# Sheet1.net
KiCad netlist of a schematic drawn in Altium Designer
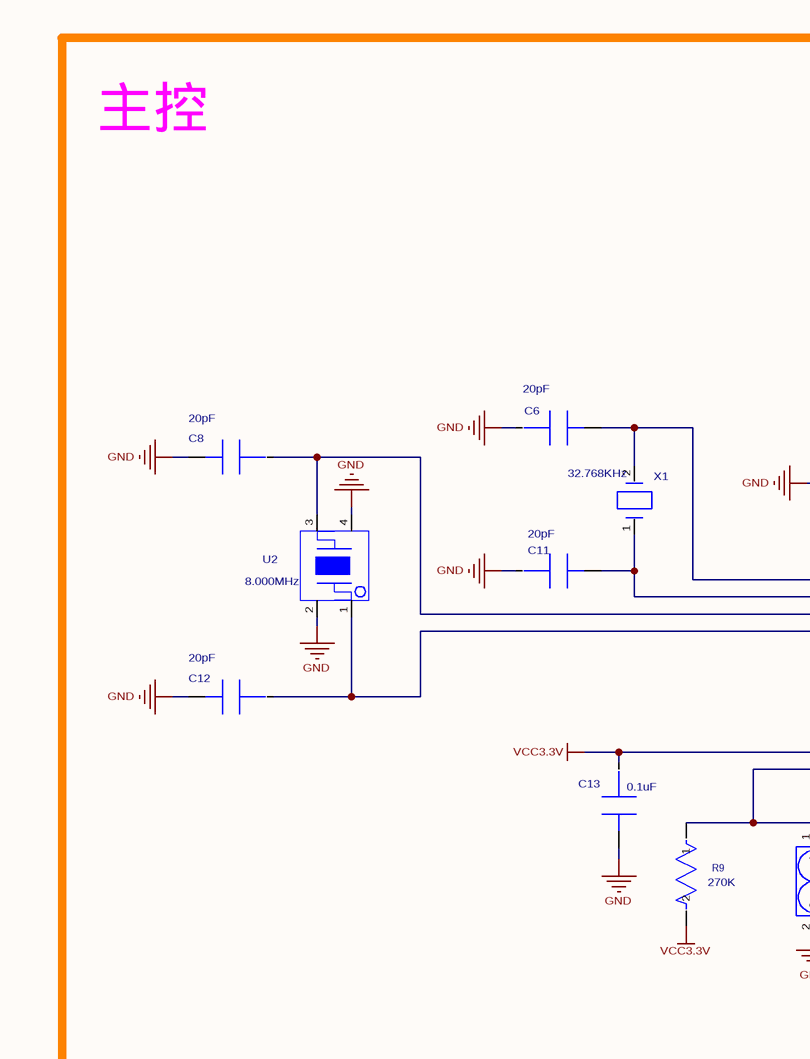
[diagram p0: Sheet1.SchDoc, top column 1 of 4]
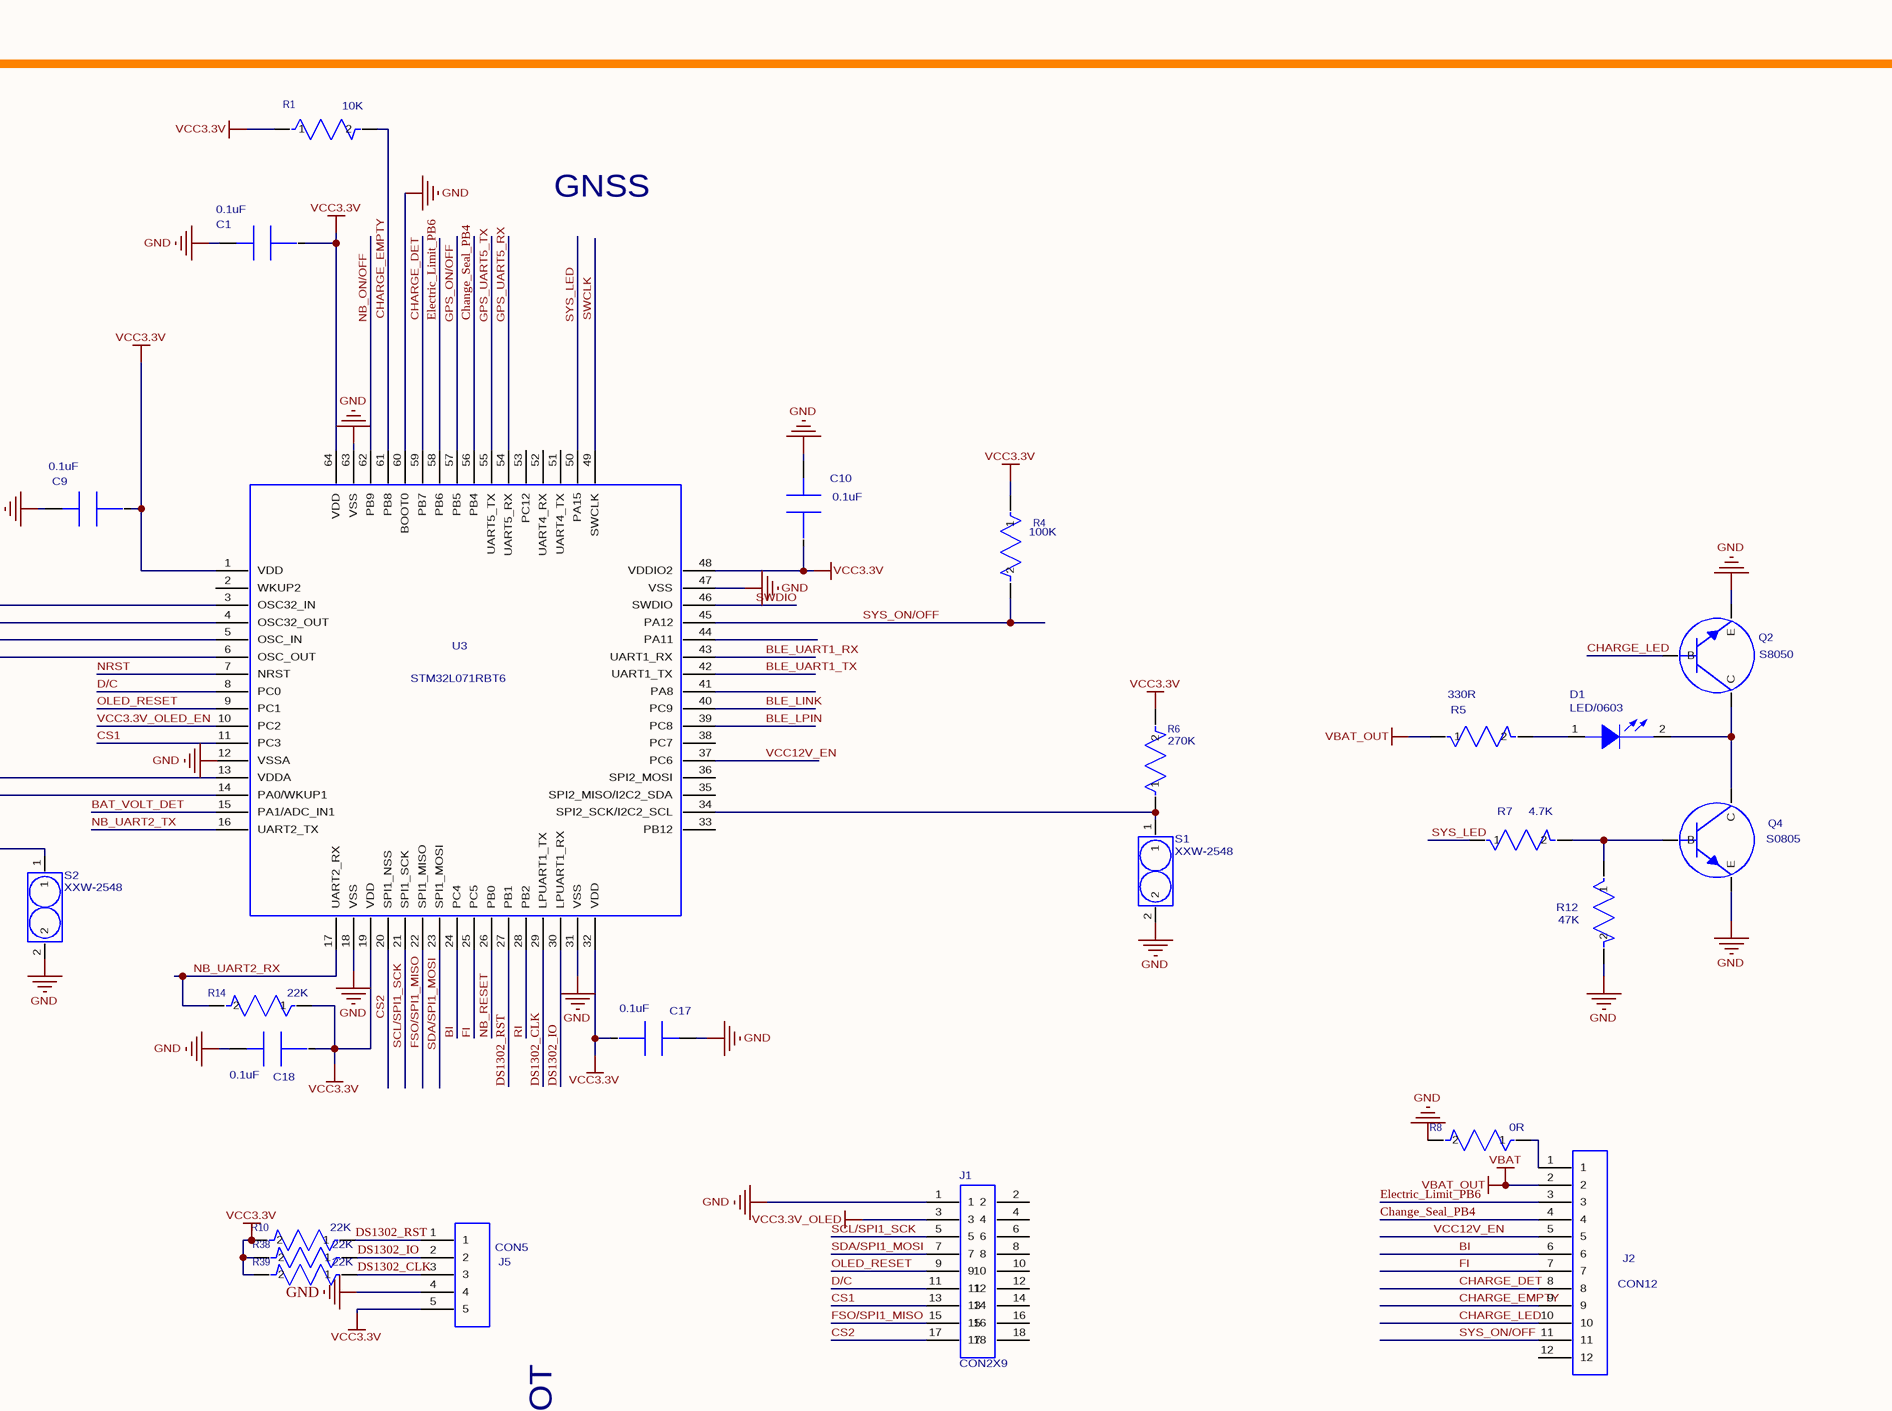
[diagram p1: Sheet1.SchDoc, top column 2 of 4]
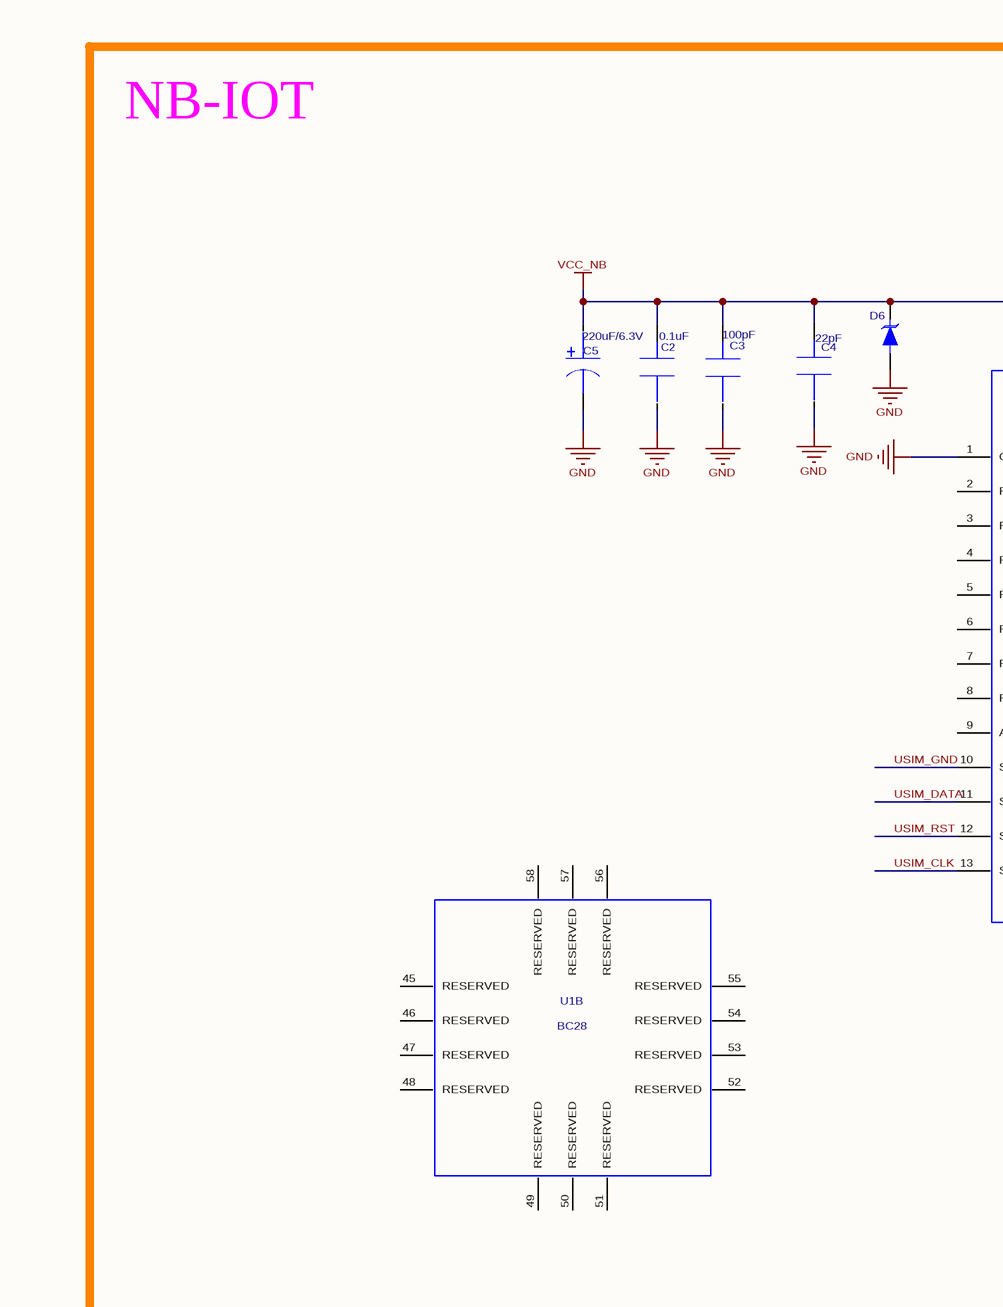
[diagram p2: Sheet1.SchDoc, top column 3 of 4]
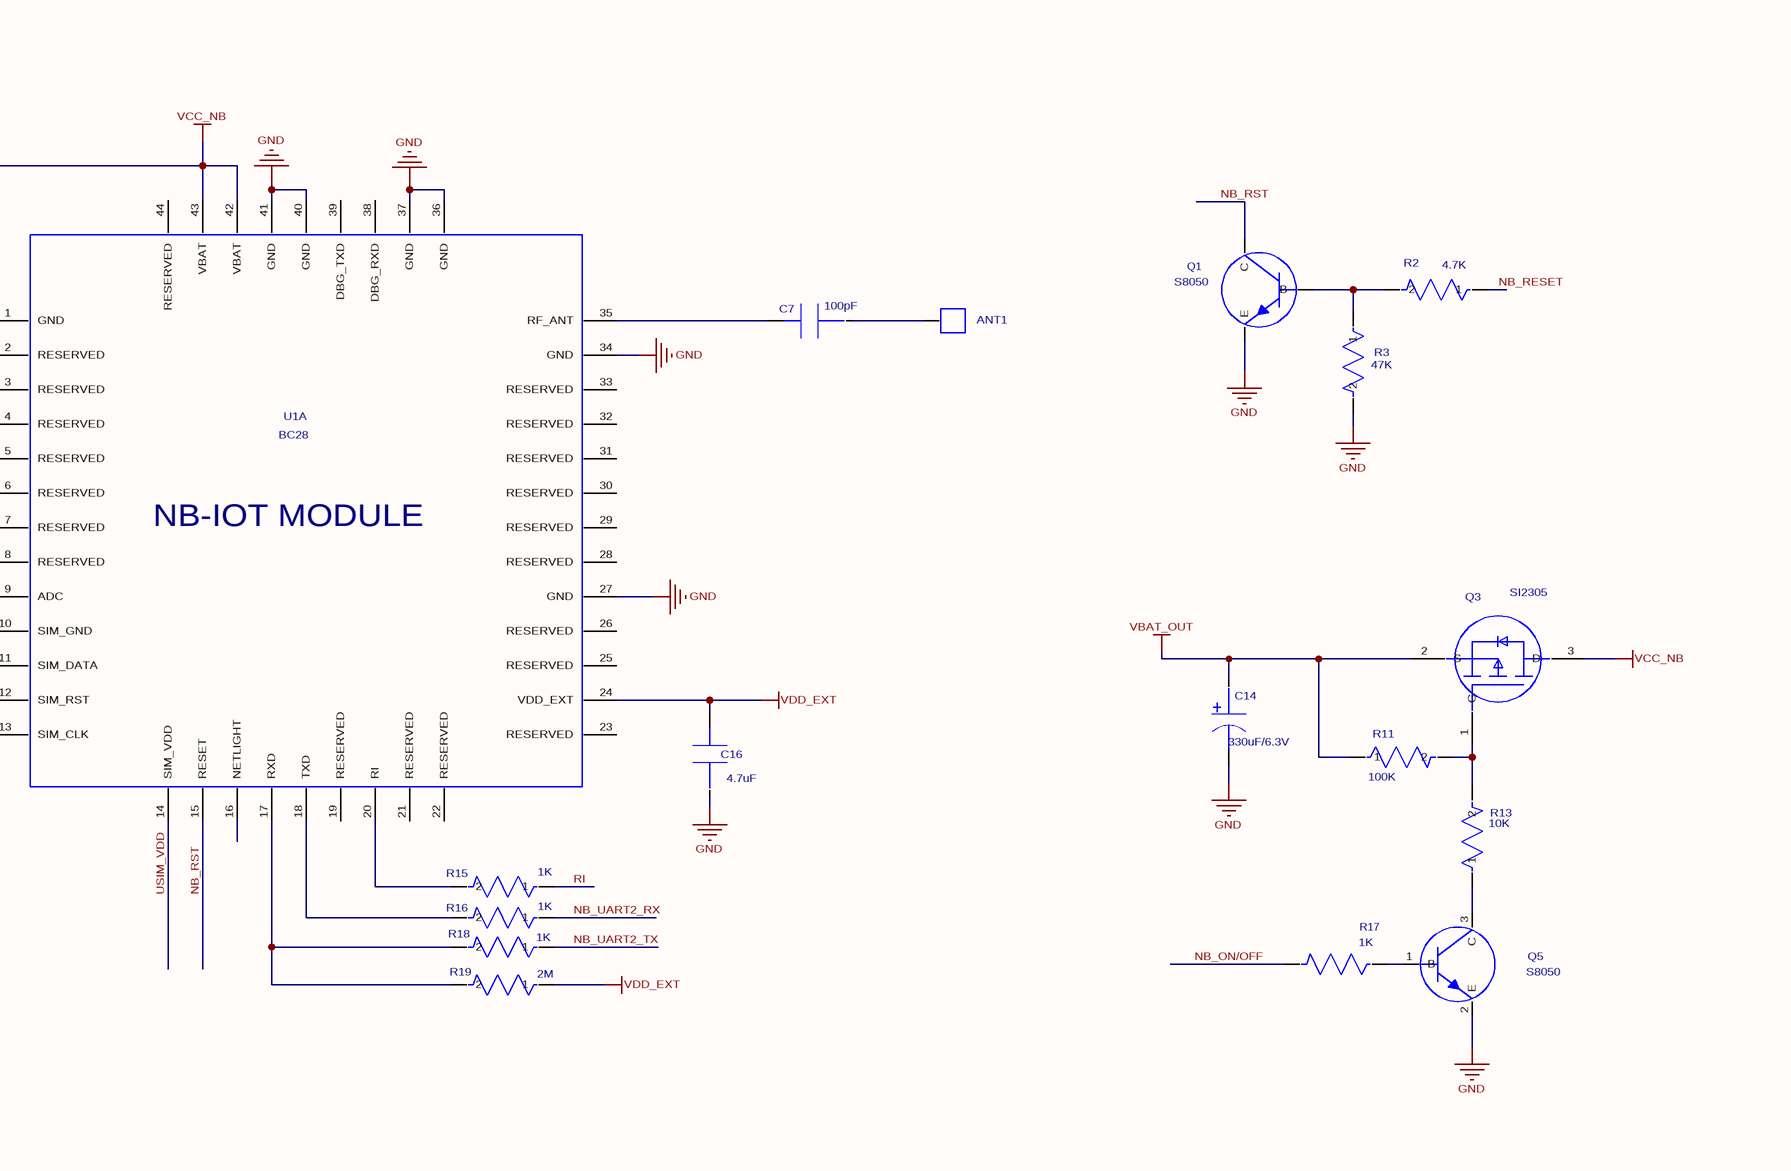
[diagram p3: Sheet1.SchDoc, top column 4 of 4]
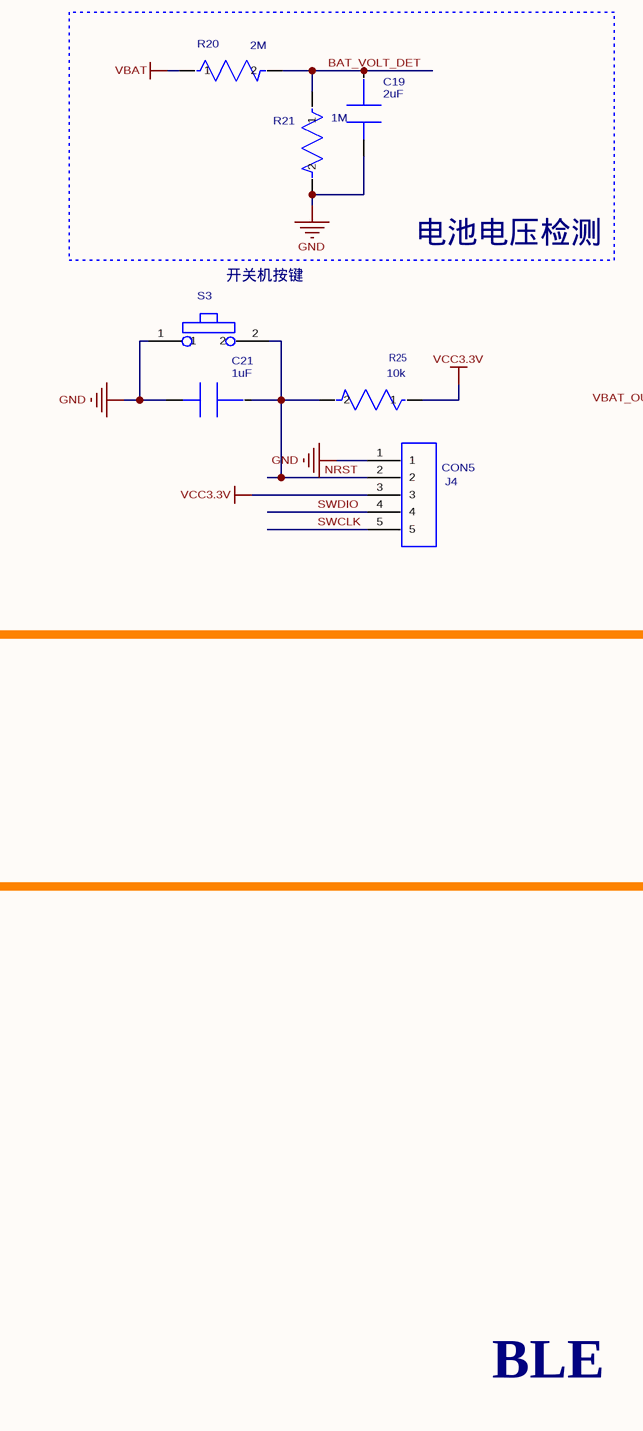
[diagram p4: Sheet1.SchDoc, centre column 1 of 4]
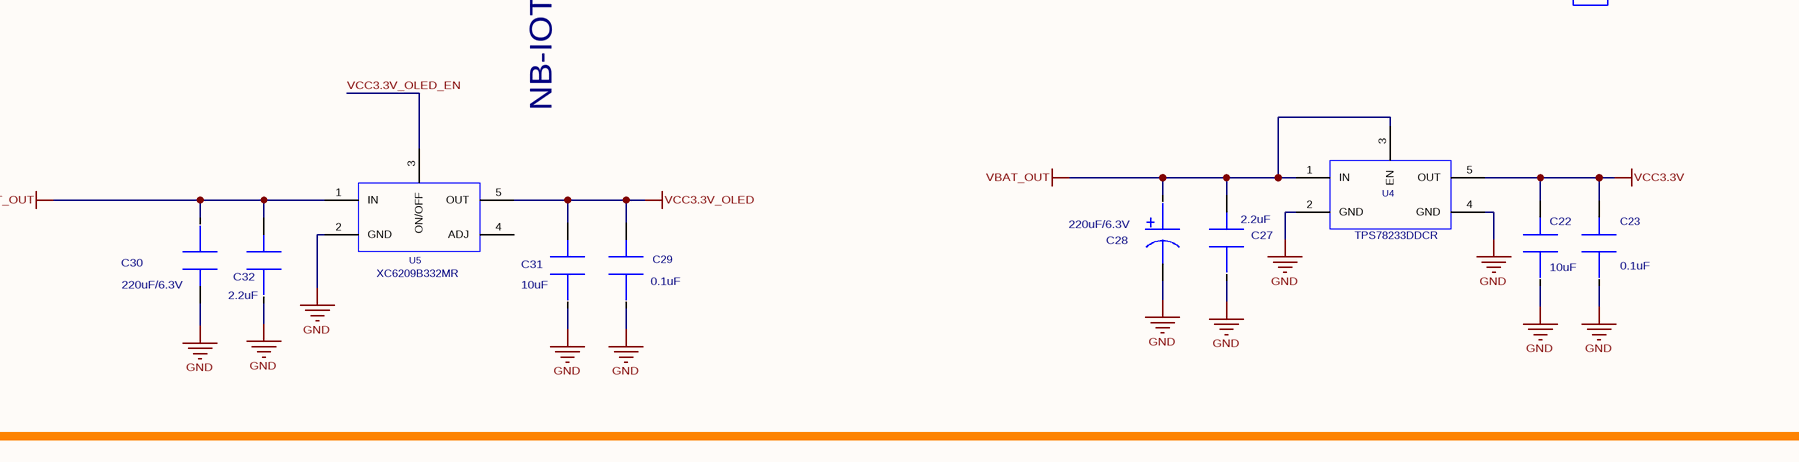
[diagram p5: Sheet1.SchDoc, centre column 2 of 4]
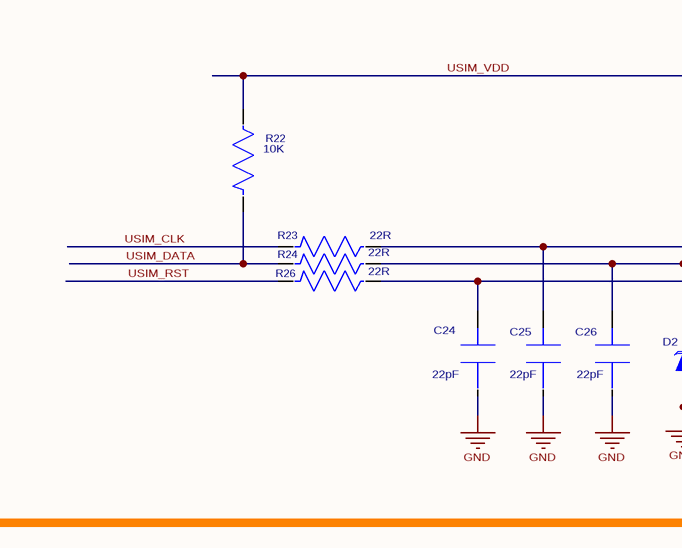
[diagram p6: Sheet1.SchDoc, centre column 3 of 4]
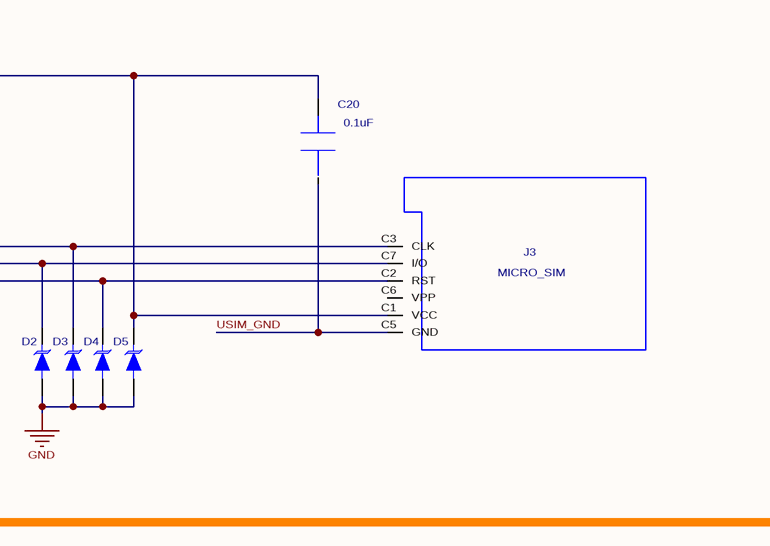
[diagram p7: Sheet1.SchDoc, centre column 4 of 4]
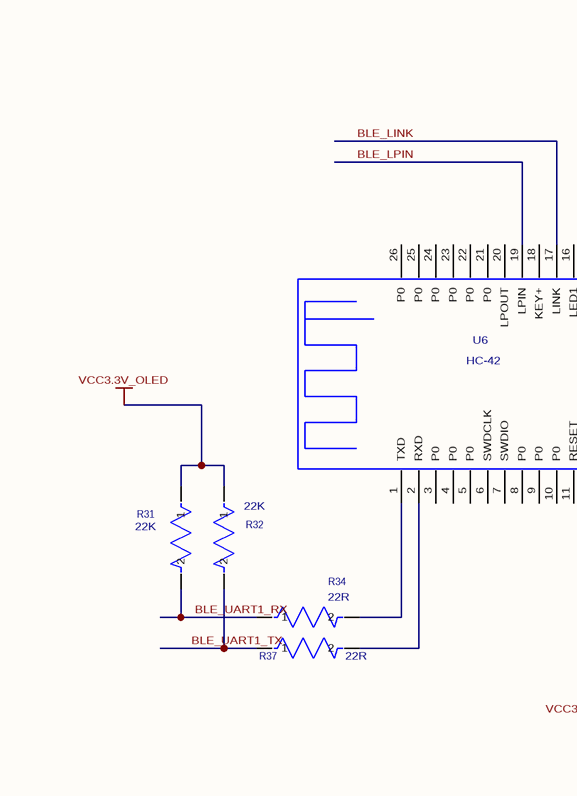
[diagram p8: Sheet1.SchDoc, bottom column 1 of 4]
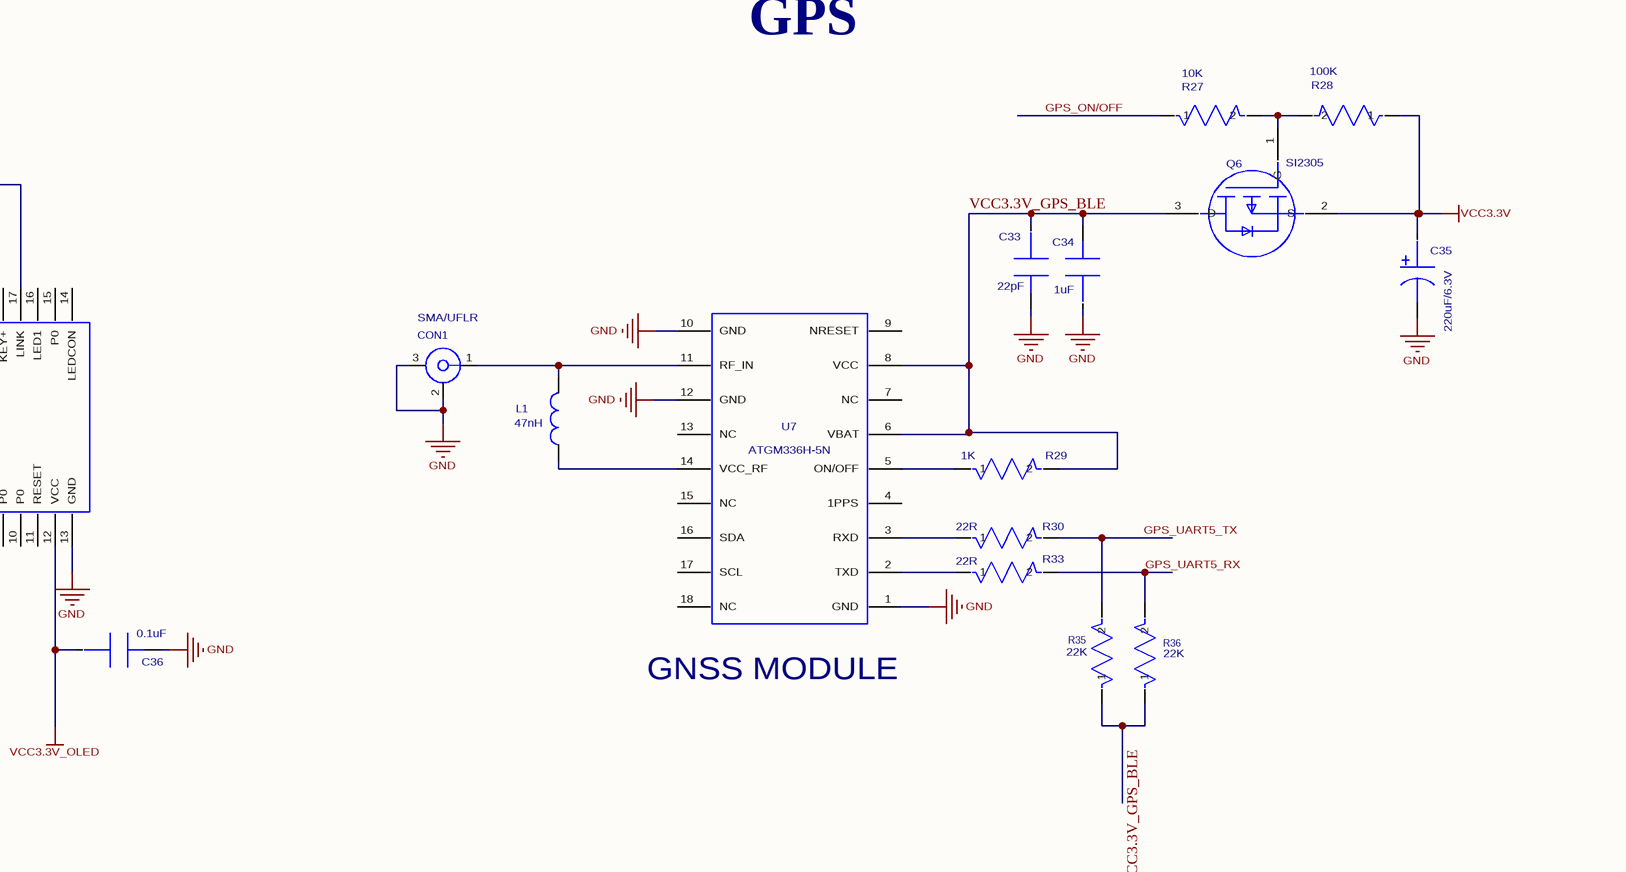
[diagram p9: Sheet1.SchDoc, bottom column 2 of 4]

(export (version "E")
  (design (tool "Eeschema 10.0.6"))
  (components
    (comp (ref "ANT1") (value "PAD") (footprint "L4G3210") (libsource (lib "*") (part "PAD")))
    (comp (ref "C1") (value "0.1uF") (footprint "C0402") (libsource (lib "*") (part "C")))
    (comp (ref "C2") (value "0.1uF") (footprint "C0402") (libsource (lib "*") (part "C")))
    (comp (ref "C3") (value "100pF") (footprint "C0402") (libsource (lib "*") (part "C")))
    (comp (ref "C4") (value "22pF") (footprint "C0402") (libsource (lib "*") (part "C")))
    (comp (ref "C5") (value "220uF/6.3V") (footprint "C1210-E") (libsource (lib "") (part "C_1")))
    (comp (ref "C6") (value "20pF") (footprint "C0402") (libsource (lib "*") (part "C")))
    (comp (ref "C7") (value "100pF") (footprint "C0402") (libsource (lib "*") (part "C")))
    (comp (ref "C8") (value "20pF") (footprint "C0402") (libsource (lib "*") (part "C")))
    (comp (ref "C9") (value "0.1uF") (footprint "C0402") (libsource (lib "*") (part "C")))
    (comp (ref "C10") (value "0.1uF") (footprint "C0402") (libsource (lib "*") (part "C")))
    (comp (ref "C11") (value "20pF") (footprint "C0402") (libsource (lib "*") (part "C")))
    (comp (ref "C12") (value "20pF") (footprint "C0402") (libsource (lib "*") (part "C")))
    (comp (ref "C13") (value "0.1uF") (footprint "C0402") (libsource (lib "*") (part "C")))
    (comp (ref "C14") (value "330uF/6.3V") (footprint "CAP6R3X5R6-SM") (libsource (lib "") (part "C_1")))
    (comp (ref "C16") (value "4.7uF") (footprint "C0603") (libsource (lib "*") (part "C")))
    (comp (ref "C17") (value "0.1uF") (footprint "C0402") (libsource (lib "*") (part "C")))
    (comp (ref "C18") (value "0.1uF") (footprint "C0402") (libsource (lib "*") (part "C")))
    (comp (ref "C19") (value "2uF") (footprint "C0402") (libsource (lib "*") (part "C")))
    (comp (ref "C20") (value "0.1uF") (footprint "C0402") (libsource (lib "*") (part "C")))
    (comp (ref "C21") (value "1uF") (footprint "C0402") (libsource (lib "*") (part "C")))
    (comp (ref "C22") (value "10uF") (footprint "C0603") (libsource (lib "*") (part "C")))
    (comp (ref "C23") (value "0.1uF") (footprint "C0402") (libsource (lib "*") (part "C")))
    (comp (ref "C24") (value "22pF") (footprint "C0402") (libsource (lib "*") (part "C")))
    (comp (ref "C25") (value "22pF") (footprint "C0402") (libsource (lib "*") (part "C")))
    (comp (ref "C26") (value "22pF") (footprint "C0402") (libsource (lib "*") (part "C")))
    (comp (ref "C27") (value "2.2uF") (footprint "C0603") (libsource (lib "*") (part "C")))
    (comp (ref "C28") (value "220uF/6.3V") (footprint "C1210-E") (libsource (lib "") (part "C_1")))
    (comp (ref "C29") (value "0.1uF") (footprint "C0402") (libsource (lib "*") (part "C")))
    (comp (ref "C30") (value "220uF/6.3V") (footprint "C1210-E") (libsource (lib "*") (part "C")))
    (comp (ref "C31") (value "10uF") (footprint "C0603") (libsource (lib "*") (part "C")))
    (comp (ref "C32") (value "2.2uF") (footprint "C0603") (libsource (lib "*") (part "C")))
    (comp (ref "C33") (value "22pF") (footprint "C0402") (libsource (lib "*") (part "C")))
    (comp (ref "C34") (value "1uF") (footprint "C0402") (libsource (lib "*") (part "C")))
    (comp (ref "C35") (value "220uF/6.3V") (footprint "C1210-E") (libsource (lib "") (part "C_1")))
    (comp (ref "C36") (value "0.1uF") (footprint "C0402") (libsource (lib "*") (part "C")))
    (comp (ref "CON1") (value "SMA/UFLR") (footprint "IPX_U.FL") (libsource (lib "*") (part "SMA/UFLR")))
    (comp (ref "D1") (value "LED/0603") (footprint "D1206") (libsource (lib "*") (part "LED/0603")))
    (comp (ref "D2")
      (value "ESDLC5V0D3")
      (footprint "SOD-323")
      (description "TVS  Vrwm=5V Vc=9.8V 2P SOD323 SMT")
      (fields (field (name "PART_NUMBER") "DLPRO000024"))
      (libsource (lib "*") (part "TVS_0"))
    )
    (comp (ref "D3")
      (value "ESDLC5V0D3")
      (footprint "SOD-323")
      (description "TVS  Vrwm=5V Vc=9.8V 2P SOD323 SMT")
      (fields (field (name "PART_NUMBER") "DLPRO000024"))
      (libsource (lib "*") (part "TVS_0"))
    )
    (comp (ref "D4")
      (value "ESDLC5V0D3")
      (footprint "SOD-323")
      (description "TVS  Vrwm=5V Vc=9.8V 2P SOD323 SMT")
      (fields (field (name "PART_NUMBER") "DLPRO000024"))
      (libsource (lib "*") (part "TVS_0"))
    )
    (comp (ref "D5")
      (value "ESDLC5V0D3")
      (footprint "SOD-323")
      (description "TVS  Vrwm=5V Vc=9.8V 2P SOD323 SMT")
      (fields (field (name "PART_NUMBER") "DLPRO000024"))
      (libsource (lib "*") (part "TVS_0"))
    )
    (comp (ref "D6")
      (value "ESDLC5V0D3")
      (footprint "SOD-323")
      (description "TVS  Vrwm=5V Vc=9.8V 2P SOD323 SMT")
      (fields (field (name "PART_NUMBER") "DLPRO000024"))
      (libsource (lib "*") (part "TVS_0"))
    )
    (comp (ref "J1") (value "CON2X9") (footprint "OLED_2X9SMT") (libsource (lib "*") (part "CON2X9")))
    (comp (ref "J2") (value "CON12") (footprint "CON_12WT") (libsource (lib "*") (part "CON12")))
    (comp (ref "J3") (value "MICRO_SIM") (footprint "MICRO_SIM") (libsource (lib "*") (part "MICRO_SIM")))
    (comp (ref "J4") (value "CON5") (footprint "SIP1X5-2R54") (libsource (lib "*") (part "CON5")))
    (comp (ref "J5") (value "CON5") (footprint "HDR1X5") (libsource (lib "*") (part "CON5")))
    (comp (ref "L1") (value "47nH") (footprint "L0402") (libsource (lib "*") (part "L")))
    (comp (ref "Q1") (value "S8050") (footprint "SOT23") (libsource (lib "*") (part "NPN-A")))
    (comp (ref "Q2") (value "S8050") (footprint "SOT23") (libsource (lib "*") (part "NPN-A")))
    (comp (ref "Q3") (value "SI2305") (footprint "SOT23") (libsource (lib "*") (part "FDN338P")))
    (comp (ref "Q4") (value "S0805") (footprint "SOT23") (libsource (lib "*") (part "NPN-A")))
    (comp (ref "Q5") (value "S8050") (footprint "SOT23") (libsource (lib "") (part "NPN-A_1")))
    (comp (ref "Q6") (value "SI2305") (footprint "SOT23") (libsource (lib "") (part "FDN338P_1")))
    (comp (ref "R1") (value "10K") (footprint "R0402") (libsource (lib "*") (part "R")))
    (comp (ref "R2") (value "4.7K") (footprint "R0402") (libsource (lib "*") (part "R")))
    (comp (ref "R3") (value "47K") (footprint "R0402") (libsource (lib "*") (part "R")))
    (comp (ref "R4") (value "100K") (footprint "R0402") (libsource (lib "*") (part "R")))
    (comp (ref "R5") (value "330R") (footprint "R0402") (libsource (lib "*") (part "R")))
    (comp (ref "R6") (value "270K") (footprint "R0402") (libsource (lib "*") (part "R")))
    (comp (ref "R7") (value "4.7K") (footprint "R0402") (libsource (lib "*") (part "R")))
    (comp (ref "R8") (value "0R") (footprint "R0603") (libsource (lib "*") (part "R")))
    (comp (ref "R9") (value "270K") (footprint "R0402") (libsource (lib "*") (part "R")))
    (comp (ref "R10") (value "22K") (footprint "R0402") (libsource (lib "*") (part "R")))
    (comp (ref "R11") (value "100K") (footprint "R0402") (libsource (lib "*") (part "R")))
    (comp (ref "R12") (value "47K") (footprint "R0402") (libsource (lib "*") (part "R")))
    (comp (ref "R13") (value "10K") (footprint "R0402") (libsource (lib "*") (part "R")))
    (comp (ref "R14") (value "22K") (footprint "R0402") (libsource (lib "*") (part "R")))
    (comp (ref "R15") (value "1K") (footprint "R0402") (libsource (lib "*") (part "R")))
    (comp (ref "R16") (value "1K") (footprint "R0402") (libsource (lib "*") (part "R")))
    (comp (ref "R17") (value "1K") (footprint "R0402") (libsource (lib "") (part "R_1")))
    (comp (ref "R18") (value "1K") (footprint "R0402") (libsource (lib "*") (part "R")))
    (comp (ref "R19") (value "2M") (footprint "R0402") (libsource (lib "*") (part "R")))
    (comp (ref "R20") (value "2M") (footprint "R0402") (libsource (lib "*") (part "R")))
    (comp (ref "R21") (value "1M") (footprint "R0402") (libsource (lib "*") (part "R")))
    (comp (ref "R22") (value "10K") (footprint "R0402") (libsource (lib "") (part "R_1")))
    (comp (ref "R23") (value "22R") (footprint "R0402") (libsource (lib "") (part "R_1")))
    (comp (ref "R24") (value "22R") (footprint "R0402") (libsource (lib "") (part "R_1")))
    (comp (ref "R25") (value "10k") (footprint "R0402") (libsource (lib "*") (part "R")))
    (comp (ref "R26") (value "22R") (footprint "R0402") (libsource (lib "") (part "R_1")))
    (comp (ref "R27") (value "10K") (footprint "R0402") (libsource (lib "*") (part "R")))
    (comp (ref "R28") (value "100K") (footprint "R0402") (libsource (lib "*") (part "R")))
    (comp (ref "R29") (value "1K") (footprint "R0402") (libsource (lib "*") (part "R")))
    (comp (ref "R30") (value "22R") (footprint "R0402") (libsource (lib "*") (part "R")))
    (comp (ref "R31") (value "22K") (footprint "R0402") (libsource (lib "*") (part "R")))
    (comp (ref "R32") (value "22K") (footprint "R0402") (libsource (lib "*") (part "R")))
    (comp (ref "R33") (value "22R") (footprint "R0402") (libsource (lib "*") (part "R")))
    (comp (ref "R34") (value "22R") (footprint "R0402") (libsource (lib "*") (part "R")))
    (comp (ref "R35") (value "22K") (footprint "R0402") (libsource (lib "*") (part "R")))
    (comp (ref "R36") (value "22K") (footprint "R0402") (libsource (lib "*") (part "R")))
    (comp (ref "R37") (value "22R") (footprint "R0402") (libsource (lib "*") (part "R")))
    (comp (ref "R38") (value "22K") (footprint "R0402") (libsource (lib "*") (part "R")))
    (comp (ref "R39") (value "22K") (footprint "R0402") (libsource (lib "*") (part "R")))
    (comp (ref "S1") (value "XXW-2548") (footprint "XXW-2548") (libsource (lib "*") (part "XXW-2548")))
    (comp (ref "S2") (value "XXW-2548") (footprint "XXW-2548") (libsource (lib "*") (part "XXW-2548")))
    (comp (ref "S3") (value "SW_3X6X5") (footprint "SW3X6X3R5") (libsource (lib "*") (part "SW_3X6X5")))
    (comp (ref "U1")
      (value "BC28")
      (footprint "BC28")
      (fields (field (name "MANUFACTURER") "QUECTEL"))
      (libsource (lib "*") (part "BC28"))
    )
    (comp (ref "U2") (value "8.000MHz") (footprint "XTAL4-5X3R2") (libsource (lib "*") (part "XTAL_3.2X2.5")))
    (comp (ref "U3")
      (value "STM32L071RBT6")
      (footprint "QFP64-0R5")
      (libsource (lib "*") (part "STM32L071RBT6"))
    )
    (comp (ref "U4") (value "TPS78233DDCR") (footprint "SOT23-5") (libsource (lib "*") (part "TPS78233DDCR")))
    (comp (ref "U5") (value "XC6209B332MR") (footprint "SOT23-5") (libsource (lib "*") (part "LP2980")))
    (comp (ref "U6") (value "HC-42") (footprint "BLEMODE") (libsource (lib "*") (part "HC-42")))
    (comp (ref "U7") (value "ATGM336H-5N") (footprint "ATGM336") (libsource (lib "*") (part "ATGM336H-5N")))
    (comp (ref "X1") (value "32.768KHz") (footprint "X_MC146") (libsource (lib "*") (part "CRYSTAL2")))
  )
  (nets
    (net (code "1") (name "/BAT_VOLT_DET") (class "Default")
      (node (ref "C19") (pin "1") (pinfunction "1_1") (pintype "passive"))
      (node (ref "R20") (pin "2") (pinfunction "2_2") (pintype "passive"))
      (node (ref "R21") (pin "1") (pinfunction "1_1") (pintype "passive"))
      (node (ref "U3") (pin "15") (pinfunction "PA1/ADC_IN1_15") (pintype "passive"))
    )
    (net (code "2") (name "/BI") (class "Default")
      (node (ref "J2") (pin "6") (pinfunction "6_6") (pintype "passive"))
      (node (ref "U3") (pin "24") (pinfunction "PC4_24") (pintype "passive"))
    )
    (net (code "3") (name "/BLE_LINK") (class "Default")
      (node (ref "U3") (pin "40") (pinfunction "PC9_40") (pintype "passive"))
      (node (ref "U6") (pin "17") (pinfunction "LINK_17") (pintype "passive"))
    )
    (net (code "4") (name "/BLE_LPIN") (class "Default")
      (node (ref "U3") (pin "39") (pinfunction "PC8_39") (pintype "passive"))
      (node (ref "U6") (pin "19") (pinfunction "LPIN_19") (pintype "passive"))
    )
    (net (code "5") (name "/BLE_UART1_RX") (class "Default")
      (node (ref "R31") (pin "2") (pinfunction "2_2") (pintype "passive"))
      (node (ref "R34") (pin "1") (pinfunction "1_1") (pintype "passive"))
      (node (ref "U3") (pin "43") (pinfunction "UART1_RX_43") (pintype "passive"))
    )
    (net (code "6") (name "/BLE_UART1_TX") (class "Default")
      (node (ref "R32") (pin "2") (pinfunction "2_2") (pintype "passive"))
      (node (ref "R37") (pin "1") (pinfunction "1_1") (pintype "passive"))
      (node (ref "U3") (pin "42") (pinfunction "UART1_TX_42") (pintype "passive"))
    )
    (net (code "7") (name "/CHARGE_DET") (class "Default")
      (node (ref "J2") (pin "8") (pinfunction "8_8") (pintype "passive"))
      (node (ref "U3") (pin "59") (pinfunction "PB7_59") (pintype "passive"))
    )
    (net (code "8") (name "/CHARGE_EMPTY") (class "Default")
      (node (ref "J2") (pin "9") (pinfunction "9_9") (pintype "passive"))
      (node (ref "R1") (pin "2") (pinfunction "2_2") (pintype "passive"))
      (node (ref "U3") (pin "61") (pinfunction "PB8_61") (pintype "passive"))
    )
    (net (code "9") (name "/CHARGE_LED") (class "Default")
      (node (ref "J2") (pin "10") (pinfunction "10_10") (pintype "passive"))
      (node (ref "Q2") (pin "1") (pinfunction "B_1") (pintype "passive"))
    )
    (net (code "10") (name "/CS1") (class "Default")
      (node (ref "J1") (pin "13") (pinfunction "13_13") (pintype "passive"))
      (node (ref "U3") (pin "11") (pinfunction "PC3_11") (pintype "passive"))
    )
    (net (code "11") (name "/CS2") (class "Default")
      (node (ref "J1") (pin "17") (pinfunction "17_17") (pintype "passive"))
      (node (ref "U3") (pin "20") (pinfunction "SPI1_NSS_20") (pintype "passive"))
    )
    (net (code "12") (name "/Change_Seal_PB4") (class "Default")
      (node (ref "J2") (pin "4") (pinfunction "4_4") (pintype "passive"))
      (node (ref "U3") (pin "56") (pinfunction "PB4_56") (pintype "passive"))
    )
    (net (code "13") (name "/DS1302_CLK") (class "Default")
      (node (ref "J5") (pin "3") (pinfunction "3_3") (pintype "passive"))
      (node (ref "R39") (pin "1") (pinfunction "1_1") (pintype "passive"))
      (node (ref "U3") (pin "29") (pinfunction "LPUART1_TX_29") (pintype "passive"))
    )
    (net (code "14") (name "/DS1302_IO") (class "Default")
      (node (ref "J5") (pin "2") (pinfunction "2_2") (pintype "passive"))
      (node (ref "R38") (pin "1") (pinfunction "1_1") (pintype "passive"))
      (node (ref "U3") (pin "30") (pinfunction "LPUART1_RX_30") (pintype "passive"))
    )
    (net (code "15") (name "/DS1302_RST") (class "Default")
      (node (ref "J5") (pin "1") (pinfunction "1_1") (pintype "passive"))
      (node (ref "R10") (pin "1") (pinfunction "1_1") (pintype "passive"))
      (node (ref "U3") (pin "27") (pinfunction "PB1_27") (pintype "passive"))
    )
    (net (code "16") (name "/D{slash}C") (class "Default")
      (node (ref "J1") (pin "11") (pinfunction "11_11") (pintype "passive"))
      (node (ref "U3") (pin "8") (pinfunction "PC0_8") (pintype "passive"))
    )
    (net (code "17") (name "/Electric_Limit_PB6") (class "Default")
      (node (ref "J2") (pin "3") (pinfunction "3_3") (pintype "passive"))
      (node (ref "U3") (pin "58") (pinfunction "PB6_58") (pintype "passive"))
    )
    (net (code "18") (name "/FI") (class "Default")
      (node (ref "J2") (pin "7") (pinfunction "7_7") (pintype "passive"))
      (node (ref "U3") (pin "25") (pinfunction "PC5_25") (pintype "passive"))
    )
    (net (code "19") (name "/FSO{slash}SPI1_MISO") (class "Default")
      (node (ref "J1") (pin "15") (pinfunction "15_15") (pintype "passive"))
      (node (ref "U3") (pin "22") (pinfunction "SPI1_MISO_22") (pintype "passive"))
    )
    (net (code "20") (name "/GPS_ON{slash}OFF") (class "Default")
      (node (ref "R27") (pin "1") (pinfunction "1_1") (pintype "passive"))
      (node (ref "U3") (pin "57") (pinfunction "PB5_57") (pintype "passive"))
    )
    (net (code "21") (name "/GPS_UART5_RX") (class "Default")
      (node (ref "R33") (pin "2") (pinfunction "2_2") (pintype "passive"))
      (node (ref "R36") (pin "2") (pinfunction "2_2") (pintype "passive"))
      (node (ref "U3") (pin "54") (pinfunction "UART5_RX_54") (pintype "passive"))
    )
    (net (code "22") (name "/GPS_UART5_TX") (class "Default")
      (node (ref "R30") (pin "2") (pinfunction "2_2") (pintype "passive"))
      (node (ref "R35") (pin "2") (pinfunction "2_2") (pintype "passive"))
      (node (ref "U3") (pin "55") (pinfunction "UART5_TX_55") (pintype "passive"))
    )
    (net (code "23") (name "/NB_ON{slash}OFF") (class "Default")
      (node (ref "R17") (pin "2") (pinfunction "2_2") (pintype "passive"))
      (node (ref "U3") (pin "62") (pinfunction "PB9_62") (pintype "passive"))
    )
    (net (code "24") (name "/NB_RESET") (class "Default")
      (node (ref "R2") (pin "1") (pinfunction "1_1") (pintype "passive"))
      (node (ref "U3") (pin "26") (pinfunction "PB0_26") (pintype "passive"))
    )
    (net (code "25") (name "/NB_RST") (class "Default")
      (node (ref "Q1") (pin "3") (pinfunction "C_3") (pintype "passive"))
      (node (ref "U1") (pin "15") (pinfunction "RESET_15") (pintype "passive"))
    )
    (net (code "26") (name "/NB_UART2_RX") (class "Default")
      (node (ref "R14") (pin "2") (pinfunction "2_2") (pintype "passive"))
      (node (ref "R16") (pin "1") (pinfunction "1_1") (pintype "passive"))
      (node (ref "U3") (pin "17") (pinfunction "UART2_RX_17") (pintype "passive"))
    )
    (net (code "27") (name "/NB_UART2_TX") (class "Default")
      (node (ref "R18") (pin "1") (pinfunction "1_1") (pintype "passive"))
      (node (ref "U3") (pin "16") (pinfunction "UART2_TX_16") (pintype "passive"))
    )
    (net (code "28") (name "/NRST") (class "Default")
      (node (ref "C21") (pin "1") (pinfunction "1_1") (pintype "passive"))
      (node (ref "J4") (pin "2") (pinfunction "2_2") (pintype "passive"))
      (node (ref "R25") (pin "2") (pinfunction "2_2") (pintype "passive"))
      (node (ref "S3") (pin "2") (pinfunction "2_2") (pintype "passive"))
      (node (ref "U3") (pin "7") (pinfunction "NRST_7") (pintype "passive"))
    )
    (net (code "29") (name "/OLED_RESET") (class "Default")
      (node (ref "J1") (pin "9") (pinfunction "9_9") (pintype "passive"))
      (node (ref "U3") (pin "9") (pinfunction "PC1_9") (pintype "passive"))
    )
    (net (code "30") (name "/RI") (class "Default")
      (node (ref "R15") (pin "1") (pinfunction "1_1") (pintype "passive"))
      (node (ref "U3") (pin "28") (pinfunction "PB2_28") (pintype "passive"))
    )
    (net (code "31") (name "/SCL{slash}SPI1_SCK") (class "Default")
      (node (ref "J1") (pin "5") (pinfunction "5_5") (pintype "passive"))
      (node (ref "U3") (pin "21") (pinfunction "SPI1_SCK_21") (pintype "passive"))
    )
    (net (code "32") (name "/SDA{slash}SPI1_MOSI") (class "Default")
      (node (ref "J1") (pin "7") (pinfunction "7_7") (pintype "passive"))
      (node (ref "U3") (pin "23") (pinfunction "SPI1_MOSI_23") (pintype "passive"))
    )
    (net (code "33") (name "/SWCLK") (class "Default")
      (node (ref "J4") (pin "5") (pinfunction "5_5") (pintype "passive"))
      (node (ref "U3") (pin "49") (pinfunction "SWCLK_49") (pintype "passive"))
    )
    (net (code "34") (name "/SWDIO") (class "Default")
      (node (ref "J4") (pin "4") (pinfunction "4_4") (pintype "passive"))
      (node (ref "U3") (pin "46") (pinfunction "SWDIO_46") (pintype "passive"))
    )
    (net (code "35") (name "/SYS_LED") (class "Default")
      (node (ref "R7") (pin "1") (pinfunction "1_1") (pintype "passive"))
      (node (ref "U3") (pin "50") (pinfunction "PA15_50") (pintype "passive"))
    )
    (net (code "36") (name "/SYS_ON{slash}OFF") (class "Default")
      (node (ref "J2") (pin "11") (pinfunction "11_11") (pintype "passive"))
      (node (ref "R4") (pin "2") (pinfunction "2_2") (pintype "passive"))
      (node (ref "U3") (pin "45") (pinfunction "PA12_45") (pintype "passive"))
    )
    (net (code "37") (name "/USIM_CLK") (class "Default")
      (node (ref "R23") (pin "2") (pinfunction "2_2") (pintype "passive"))
      (node (ref "U1") (pin "13") (pinfunction "SIM_CLK_13") (pintype "passive"))
    )
    (net (code "38") (name "/USIM_DATA") (class "Default")
      (node (ref "R22") (pin "2") (pinfunction "2_2") (pintype "passive"))
      (node (ref "R24") (pin "2") (pinfunction "2_2") (pintype "passive"))
      (node (ref "U1") (pin "11") (pinfunction "SIM_DATA_11") (pintype "passive"))
    )
    (net (code "39") (name "/USIM_GND") (class "Default")
      (node (ref "C20") (pin "1") (pinfunction "1_1") (pintype "passive"))
      (node (ref "J3") (pin "C5") (pinfunction "GND_C5") (pintype "passive"))
      (node (ref "U1") (pin "10") (pinfunction "SIM_GND_10") (pintype "passive"))
    )
    (net (code "40") (name "/USIM_RST") (class "Default")
      (node (ref "R26") (pin "2") (pinfunction "2_2") (pintype "passive"))
      (node (ref "U1") (pin "12") (pinfunction "SIM_RST_12") (pintype "passive"))
    )
    (net (code "41") (name "/USIM_VDD") (class "Default")
      (node (ref "C20") (pin "2") (pinfunction "2_2") (pintype "passive"))
      (node (ref "D5") (pin "2") (pinfunction "CATHODE_2") (pintype "passive"))
      (node (ref "J3") (pin "C1") (pinfunction "VCC_C1") (pintype "passive"))
      (node (ref "R22") (pin "1") (pinfunction "1_1") (pintype "passive"))
      (node (ref "U1") (pin "14") (pinfunction "SIM_VDD_14") (pintype "passive"))
    )
    (net (code "42") (name "/VCC3.3V_GPS_BLE") (class "Default")
      (node (ref "C33") (pin "1") (pinfunction "1_1") (pintype "passive"))
      (node (ref "C34") (pin "2") (pinfunction "2_2") (pintype "passive"))
      (node (ref "Q6") (pin "3") (pinfunction "D_3") (pintype "passive"))
      (node (ref "R29") (pin "2") (pinfunction "2_2") (pintype "passive"))
      (node (ref "R35") (pin "1") (pinfunction "1_1") (pintype "passive"))
      (node (ref "R36") (pin "1") (pinfunction "1_1") (pintype "passive"))
      (node (ref "U7") (pin "6") (pinfunction "VBAT_6") (pintype "passive"))
      (node (ref "U7") (pin "8") (pinfunction "VCC_8") (pintype "passive"))
    )
    (net (code "43") (name "/VCC3.3V_OLED_EN") (class "Default")
      (node (ref "U3") (pin "10") (pinfunction "PC2_10") (pintype "passive"))
      (node (ref "U5") (pin "3") (pinfunction "ON/OFF_3") (pintype "passive"))
    )
    (net (code "44") (name "/VCC12V_EN") (class "Default")
      (node (ref "J2") (pin "5") (pinfunction "5_5") (pintype "passive"))
      (node (ref "U3") (pin "37") (pinfunction "PC6_37") (pintype "passive"))
    )
    (net (code "45") (name "GND") (class "Default")
      (node (ref "C1") (pin "2") (pinfunction "2_2") (pintype "passive"))
      (node (ref "C10") (pin "2") (pinfunction "2_2") (pintype "passive"))
      (node (ref "C11") (pin "1") (pinfunction "1_1") (pintype "passive"))
      (node (ref "C12") (pin "2") (pinfunction "2_2") (pintype "passive"))
      (node (ref "C13") (pin "2") (pinfunction "2_2") (pintype "passive"))
      (node (ref "C14") (pin "2") (pinfunction "2_2") (pintype "passive"))
      (node (ref "C16") (pin "1") (pinfunction "1_1") (pintype "passive"))
      (node (ref "C17") (pin "2") (pinfunction "2_2") (pintype "passive"))
      (node (ref "C18") (pin "2") (pinfunction "2_2") (pintype "passive"))
      (node (ref "C19") (pin "2") (pinfunction "2_2") (pintype "passive"))
      (node (ref "C2") (pin "1") (pinfunction "1_1") (pintype "passive"))
      (node (ref "C21") (pin "2") (pinfunction "2_2") (pintype "passive"))
      (node (ref "C22") (pin "1") (pinfunction "1_1") (pintype "passive"))
      (node (ref "C23") (pin "1") (pinfunction "1_1") (pintype "passive"))
      (node (ref "C24") (pin "1") (pinfunction "1_1") (pintype "passive"))
      (node (ref "C25") (pin "1") (pinfunction "1_1") (pintype "passive"))
      (node (ref "C26") (pin "1") (pinfunction "1_1") (pintype "passive"))
      (node (ref "C27") (pin "1") (pinfunction "1_1") (pintype "passive"))
      (node (ref "C28") (pin "2") (pinfunction "2_2") (pintype "passive"))
      (node (ref "C29") (pin "1") (pinfunction "1_1") (pintype "passive"))
      (node (ref "C3") (pin "1") (pinfunction "1_1") (pintype "passive"))
      (node (ref "C30") (pin "2") (pinfunction "2_2") (pintype "passive"))
      (node (ref "C31") (pin "1") (pinfunction "1_1") (pintype "passive"))
      (node (ref "C32") (pin "1") (pinfunction "1_1") (pintype "passive"))
      (node (ref "C33") (pin "2") (pinfunction "2_2") (pintype "passive"))
      (node (ref "C34") (pin "1") (pinfunction "1_1") (pintype "passive"))
      (node (ref "C35") (pin "2") (pinfunction "2_2") (pintype "passive"))
      (node (ref "C36") (pin "2") (pinfunction "2_2") (pintype "passive"))
      (node (ref "C4") (pin "1") (pinfunction "1_1") (pintype "passive"))
      (node (ref "C5") (pin "2") (pinfunction "2_2") (pintype "passive"))
      (node (ref "C6") (pin "1") (pinfunction "1_1") (pintype "passive"))
      (node (ref "C8") (pin "2") (pinfunction "2_2") (pintype "passive"))
      (node (ref "C9") (pin "2") (pinfunction "2_2") (pintype "passive"))
      (node (ref "CON1") (pin "2") (pinfunction "2_2") (pintype "passive"))
      (node (ref "CON1") (pin "3") (pinfunction "GNDA_3") (pintype "passive"))
      (node (ref "D2") (pin "1") (pinfunction "ANODE_1") (pintype "passive"))
      (node (ref "D3") (pin "1") (pinfunction "ANODE_1") (pintype "passive"))
      (node (ref "D4") (pin "1") (pinfunction "ANODE_1") (pintype "passive"))
      (node (ref "D5") (pin "1") (pinfunction "ANODE_1") (pintype "passive"))
      (node (ref "D6") (pin "1") (pinfunction "ANODE_1") (pintype "passive"))
      (node (ref "J1") (pin "1") (pinfunction "1_1") (pintype "passive"))
      (node (ref "J4") (pin "1") (pinfunction "1_1") (pintype "passive"))
      (node (ref "J5") (pin "4") (pinfunction "4_4") (pintype "passive"))
      (node (ref "Q1") (pin "2") (pinfunction "E_2") (pintype "passive"))
      (node (ref "Q2") (pin "2") (pinfunction "E_2") (pintype "passive"))
      (node (ref "Q4") (pin "2") (pinfunction "E_2") (pintype "passive"))
      (node (ref "Q5") (pin "2") (pinfunction "E_2") (pintype "passive"))
      (node (ref "R12") (pin "2") (pinfunction "2_2") (pintype "passive"))
      (node (ref "R21") (pin "2") (pinfunction "2_2") (pintype "passive"))
      (node (ref "R3") (pin "2") (pinfunction "2_2") (pintype "passive"))
      (node (ref "R8") (pin "2") (pinfunction "2_2") (pintype "passive"))
      (node (ref "S1") (pin "2") (pinfunction "2_2") (pintype "passive"))
      (node (ref "S2") (pin "2") (pinfunction "2_2") (pintype "passive"))
      (node (ref "S3") (pin "1") (pinfunction "1_1") (pintype "passive"))
      (node (ref "U1") (pin "1") (pinfunction "GND_1") (pintype "passive"))
      (node (ref "U1") (pin "27") (pinfunction "GND_27") (pintype "passive"))
      (node (ref "U1") (pin "34") (pinfunction "GND_34") (pintype "passive"))
      (node (ref "U1") (pin "36") (pinfunction "GND_36") (pintype "passive"))
      (node (ref "U1") (pin "37") (pinfunction "GND_37") (pintype "passive"))
      (node (ref "U1") (pin "40") (pinfunction "GND_40") (pintype "passive"))
      (node (ref "U1") (pin "41") (pinfunction "GND_41") (pintype "passive"))
      (node (ref "U2") (pin "2") (pinfunction "NC_2") (pintype "passive"))
      (node (ref "U2") (pin "4") (pinfunction "NC_4") (pintype "passive"))
      (node (ref "U3") (pin "12") (pinfunction "VSSA_12") (pintype "passive"))
      (node (ref "U3") (pin "18") (pinfunction "VSS_18") (pintype "passive"))
      (node (ref "U3") (pin "31") (pinfunction "VSS_31") (pintype "passive"))
      (node (ref "U3") (pin "47") (pinfunction "VSS_47") (pintype "passive"))
      (node (ref "U3") (pin "60") (pinfunction "BOOT0_60") (pintype "passive"))
      (node (ref "U3") (pin "63") (pinfunction "VSS_63") (pintype "passive"))
      (node (ref "U4") (pin "2") (pinfunction "GND_2") (pintype "passive"))
      (node (ref "U4") (pin "4") (pinfunction "GND_4") (pintype "passive"))
      (node (ref "U5") (pin "2") (pinfunction "GND_2") (pintype "passive"))
      (node (ref "U6") (pin "13") (pinfunction "GND_13") (pintype "passive"))
      (node (ref "U7") (pin "1") (pinfunction "GND_1") (pintype "passive"))
      (node (ref "U7") (pin "10") (pinfunction "GND_10") (pintype "passive"))
      (node (ref "U7") (pin "12") (pinfunction "GND_12") (pintype "passive"))
    )
    (net (code "46") (name "Net-(ANT1-Pad1)") (class "Default")
      (node (ref "ANT1") (pin "1") (pinfunction "1_1") (pintype "passive"))
      (node (ref "C7") (pin "1") (pinfunction "1_1") (pintype "passive"))
    )
    (net (code "47") (name "Net-(D1-ANODE)") (class "Default")
      (node (ref "D1") (pin "1") (pinfunction "ANODE_1") (pintype "passive"))
      (node (ref "R5") (pin "2") (pinfunction "2_2") (pintype "passive"))
    )
    (net (code "48") (name "Net-(D1-CATHODE)") (class "Default")
      (node (ref "D1") (pin "2") (pinfunction "CATHODE_2") (pintype "passive"))
      (node (ref "Q2") (pin "3") (pinfunction "C_3") (pintype "passive"))
      (node (ref "Q4") (pin "3") (pinfunction "C_3") (pintype "passive"))
    )
    (net (code "49") (name "Net-(D2-CATHODE)") (class "Default")
      (node (ref "C26") (pin "2") (pinfunction "2_2") (pintype "passive"))
      (node (ref "D2") (pin "2") (pinfunction "CATHODE_2") (pintype "passive"))
      (node (ref "J3") (pin "C7") (pinfunction "I/O_C7") (pintype "passive"))
      (node (ref "R24") (pin "1") (pinfunction "1_1") (pintype "passive"))
    )
    (net (code "50") (name "Net-(D3-CATHODE)") (class "Default")
      (node (ref "C25") (pin "2") (pinfunction "2_2") (pintype "passive"))
      (node (ref "D3") (pin "2") (pinfunction "CATHODE_2") (pintype "passive"))
      (node (ref "J3") (pin "C3") (pinfunction "CLK_C3") (pintype "passive"))
      (node (ref "R23") (pin "1") (pinfunction "1_1") (pintype "passive"))
    )
    (net (code "51") (name "Net-(D4-CATHODE)") (class "Default")
      (node (ref "C24") (pin "2") (pinfunction "2_2") (pintype "passive"))
      (node (ref "D4") (pin "2") (pinfunction "CATHODE_2") (pintype "passive"))
      (node (ref "J3") (pin "C2") (pinfunction "RST_C2") (pintype "passive"))
      (node (ref "R26") (pin "1") (pinfunction "1_1") (pintype "passive"))
    )
    (net (code "52") (name "Net-(J2-Pad1)") (class "Default")
      (node (ref "J2") (pin "1") (pinfunction "1_1") (pintype "passive"))
      (node (ref "R8") (pin "1") (pinfunction "1_1") (pintype "passive"))
    )
    (net (code "53") (name "Net-(Q1-B)") (class "Default")
      (node (ref "Q1") (pin "1") (pinfunction "B_1") (pintype "passive"))
      (node (ref "R2") (pin "2") (pinfunction "2_2") (pintype "passive"))
      (node (ref "R3") (pin "1") (pinfunction "1_1") (pintype "passive"))
    )
    (net (code "54") (name "Net-(Q3-G)") (class "Default")
      (node (ref "Q3") (pin "1") (pinfunction "G_1") (pintype "passive"))
      (node (ref "R11") (pin "2") (pinfunction "2_2") (pintype "passive"))
      (node (ref "R13") (pin "2") (pinfunction "2_2") (pintype "passive"))
    )
    (net (code "55") (name "Net-(Q4-B)") (class "Default")
      (node (ref "Q4") (pin "1") (pinfunction "B_1") (pintype "passive"))
      (node (ref "R12") (pin "1") (pinfunction "1_1") (pintype "passive"))
      (node (ref "R7") (pin "2") (pinfunction "2_2") (pintype "passive"))
    )
    (net (code "56") (name "Net-(Q5-B)") (class "Default")
      (node (ref "Q5") (pin "1") (pinfunction "B_1") (pintype "passive"))
      (node (ref "R17") (pin "1") (pinfunction "1_1") (pintype "passive"))
    )
    (net (code "57") (name "Net-(Q5-C)") (class "Default")
      (node (ref "Q5") (pin "3") (pinfunction "C_3") (pintype "passive"))
      (node (ref "R13") (pin "1") (pinfunction "1_1") (pintype "passive"))
    )
    (net (code "58") (name "Net-(Q6-G)") (class "Default")
      (node (ref "Q6") (pin "1") (pinfunction "G_1") (pintype "passive"))
      (node (ref "R27") (pin "2") (pinfunction "2_2") (pintype "passive"))
      (node (ref "R28") (pin "2") (pinfunction "2_2") (pintype "passive"))
    )
    (net (code "59") (name "Net-(U1A-RF_ANT)") (class "Default")
      (node (ref "C7") (pin "2") (pinfunction "2_2") (pintype "passive"))
      (node (ref "U1") (pin "35") (pinfunction "RF_ANT_35") (pintype "passive"))
    )
    (net (code "60") (name "Net-(U1A-RI)") (class "Default")
      (node (ref "R15") (pin "2") (pinfunction "2_2") (pintype "passive"))
      (node (ref "U1") (pin "20") (pinfunction "RI_20") (pintype "passive"))
    )
    (net (code "61") (name "Net-(U1A-RXD)") (class "Default")
      (node (ref "R18") (pin "2") (pinfunction "2_2") (pintype "passive"))
      (node (ref "R19") (pin "2") (pinfunction "2_2") (pintype "passive"))
      (node (ref "U1") (pin "17") (pinfunction "RXD_17") (pintype "passive"))
    )
    (net (code "62") (name "Net-(U1A-TXD)") (class "Default")
      (node (ref "R16") (pin "2") (pinfunction "2_2") (pintype "passive"))
      (node (ref "U1") (pin "18") (pinfunction "TXD_18") (pintype "passive"))
    )
    (net (code "63") (name "Net-(U2-X1)") (class "Default")
      (node (ref "C12") (pin "1") (pinfunction "1_1") (pintype "passive"))
      (node (ref "U2") (pin "1") (pinfunction "X1_1") (pintype "passive"))
      (node (ref "U3") (pin "6") (pinfunction "OSC_OUT_6") (pintype "passive"))
    )
    (net (code "64") (name "Net-(U2-X2)") (class "Default")
      (node (ref "C8") (pin "1") (pinfunction "1_1") (pintype "passive"))
      (node (ref "U2") (pin "3") (pinfunction "X2_3") (pintype "passive"))
      (node (ref "U3") (pin "5") (pinfunction "OSC_IN_5") (pintype "passive"))
    )
    (net (code "65") (name "Net-(U3-OSC32_IN)") (class "Default")
      (node (ref "C6") (pin "2") (pinfunction "2_2") (pintype "passive"))
      (node (ref "U3") (pin "3") (pinfunction "OSC32_IN_3") (pintype "passive"))
      (node (ref "X1") (pin "2") (pinfunction "2_2") (pintype "passive"))
    )
    (net (code "66") (name "Net-(U3-OSC32_OUT)") (class "Default")
      (node (ref "C11") (pin "2") (pinfunction "2_2") (pintype "passive"))
      (node (ref "U3") (pin "4") (pinfunction "OSC32_OUT_4") (pintype "passive"))
      (node (ref "X1") (pin "1") (pinfunction "1_1") (pintype "passive"))
    )
    (net (code "67") (name "Net-(U3-PA0{slash}WKUP1)") (class "Default")
      (node (ref "R9") (pin "1") (pinfunction "1_1") (pintype "passive"))
      (node (ref "S2") (pin "1") (pinfunction "1_1") (pintype "passive"))
      (node (ref "U3") (pin "14") (pinfunction "PA0/WKUP1_14") (pintype "passive"))
    )
    (net (code "68") (name "Net-(U3-SPI2_SCK{slash}I2C2_SCL)") (class "Default")
      (node (ref "R6") (pin "1") (pinfunction "1_1") (pintype "passive"))
      (node (ref "S1") (pin "1") (pinfunction "1_1") (pintype "passive"))
      (node (ref "U3") (pin "34") (pinfunction "SPI2_SCK/I2C2_SCL_34") (pintype "passive"))
    )
    (net (code "69") (name "Net-(U6-RXD)") (class "Default")
      (node (ref "R37") (pin "2") (pinfunction "2_2") (pintype "passive"))
      (node (ref "U6") (pin "2") (pinfunction "RXD_2") (pintype "passive"))
    )
    (net (code "70") (name "Net-(U6-TXD)") (class "Default")
      (node (ref "R34") (pin "2") (pinfunction "2_2") (pintype "passive"))
      (node (ref "U6") (pin "1") (pinfunction "TXD_1") (pintype "passive"))
    )
    (net (code "71") (name "Net-(U7-ON{slash}OFF)") (class "Default")
      (node (ref "R29") (pin "1") (pinfunction "1_1") (pintype "passive"))
      (node (ref "U7") (pin "5") (pinfunction "ON/OFF_5") (pintype "passive"))
    )
    (net (code "72") (name "Net-(U7-RF_IN)") (class "Default")
      (node (ref "CON1") (pin "1") (pinfunction "1_1") (pintype "passive"))
      (node (ref "L1") (pin "1") (pinfunction "1_1") (pintype "passive"))
      (node (ref "U7") (pin "11") (pinfunction "RF_IN_11") (pintype "passive"))
    )
    (net (code "73") (name "Net-(U7-RXD)") (class "Default")
      (node (ref "R30") (pin "1") (pinfunction "1_1") (pintype "passive"))
      (node (ref "U7") (pin "3") (pinfunction "RXD_3") (pintype "passive"))
    )
    (net (code "74") (name "Net-(U7-TXD)") (class "Default")
      (node (ref "R33") (pin "1") (pinfunction "1_1") (pintype "passive"))
      (node (ref "U7") (pin "2") (pinfunction "TXD_2") (pintype "passive"))
    )
    (net (code "75") (name "Net-(U7-VCC_RF)") (class "Default")
      (node (ref "L1") (pin "2") (pinfunction "2_2") (pintype "passive"))
      (node (ref "U7") (pin "14") (pinfunction "VCC_RF_14") (pintype "passive"))
    )
    (net (code "76") (name "VBAT") (class "Default")
      (node (ref "C14") (pin "1") (pinfunction "1_1") (pintype "passive"))
      (node (ref "C27") (pin "2") (pinfunction "2_2") (pintype "passive"))
      (node (ref "C28") (pin "1") (pinfunction "1_1") (pintype "passive"))
      (node (ref "C30") (pin "1") (pinfunction "1_1") (pintype "passive"))
      (node (ref "C32") (pin "2") (pinfunction "2_2") (pintype "passive"))
      (node (ref "J2") (pin "2") (pinfunction "2_2") (pintype "passive"))
      (node (ref "Q3") (pin "2") (pinfunction "S_2") (pintype "passive"))
      (node (ref "R11") (pin "1") (pinfunction "1_1") (pintype "passive"))
      (node (ref "R20") (pin "1") (pinfunction "1_1") (pintype "passive"))
      (node (ref "R5") (pin "1") (pinfunction "1_1") (pintype "passive"))
      (node (ref "U4") (pin "1") (pinfunction "IN_1") (pintype "passive"))
      (node (ref "U4") (pin "3") (pinfunction "EN_3") (pintype "passive"))
      (node (ref "U5") (pin "1") (pinfunction "IN_1") (pintype "passive"))
    )
    (net (code "77") (name "VCC3.3V") (class "Default")
      (node (ref "C1") (pin "1") (pinfunction "1_1") (pintype "passive"))
      (node (ref "C10") (pin "1") (pinfunction "1_1") (pintype "passive"))
      (node (ref "C13") (pin "1") (pinfunction "1_1") (pintype "passive"))
      (node (ref "C17") (pin "1") (pinfunction "1_1") (pintype "passive"))
      (node (ref "C18") (pin "1") (pinfunction "1_1") (pintype "passive"))
      (node (ref "C22") (pin "2") (pinfunction "2_2") (pintype "passive"))
      (node (ref "C23") (pin "2") (pinfunction "2_2") (pintype "passive"))
      (node (ref "C35") (pin "1") (pinfunction "1_1") (pintype "passive"))
      (node (ref "C9") (pin "1") (pinfunction "1_1") (pintype "passive"))
      (node (ref "J4") (pin "3") (pinfunction "3_3") (pintype "passive"))
      (node (ref "J5") (pin "5") (pinfunction "5_5") (pintype "passive"))
      (node (ref "Q6") (pin "2") (pinfunction "S_2") (pintype "passive"))
      (node (ref "R1") (pin "1") (pinfunction "1_1") (pintype "passive"))
      (node (ref "R10") (pin "2") (pinfunction "2_2") (pintype "passive"))
      (node (ref "R14") (pin "1") (pinfunction "1_1") (pintype "passive"))
      (node (ref "R25") (pin "1") (pinfunction "1_1") (pintype "passive"))
      (node (ref "R28") (pin "1") (pinfunction "1_1") (pintype "passive"))
      (node (ref "R38") (pin "2") (pinfunction "2_2") (pintype "passive"))
      (node (ref "R39") (pin "2") (pinfunction "2_2") (pintype "passive"))
      (node (ref "R4") (pin "1") (pinfunction "1_1") (pintype "passive"))
      (node (ref "R6") (pin "2") (pinfunction "2_2") (pintype "passive"))
      (node (ref "R9") (pin "2") (pinfunction "2_2") (pintype "passive"))
      (node (ref "U3") (pin "1") (pinfunction "VDD_1") (pintype "passive"))
      (node (ref "U3") (pin "13") (pinfunction "VDDA_13") (pintype "passive"))
      (node (ref "U3") (pin "19") (pinfunction "VDD_19") (pintype "passive"))
      (node (ref "U3") (pin "32") (pinfunction "VDD_32") (pintype "passive"))
      (node (ref "U3") (pin "48") (pinfunction "VDDIO2_48") (pintype "passive"))
      (node (ref "U3") (pin "64") (pinfunction "VDD_64") (pintype "passive"))
      (node (ref "U4") (pin "5") (pinfunction "OUT_5") (pintype "passive"))
    )
    (net (code "78") (name "VCC3.3V_OLED") (class "Default")
      (node (ref "C29") (pin "2") (pinfunction "2_2") (pintype "passive"))
      (node (ref "C31") (pin "2") (pinfunction "2_2") (pintype "passive"))
      (node (ref "C36") (pin "1") (pinfunction "1_1") (pintype "passive"))
      (node (ref "J1") (pin "3") (pinfunction "3_3") (pintype "passive"))
      (node (ref "R31") (pin "1") (pinfunction "1_1") (pintype "passive"))
      (node (ref "R32") (pin "1") (pinfunction "1_1") (pintype "passive"))
      (node (ref "U5") (pin "5") (pinfunction "OUT_5") (pintype "passive"))
      (node (ref "U6") (pin "12") (pinfunction "VCC_12") (pintype "passive"))
    )
    (net (code "79") (name "VCC_NB") (class "Default")
      (node (ref "C2") (pin "2") (pinfunction "2_2") (pintype "passive"))
      (node (ref "C3") (pin "2") (pinfunction "2_2") (pintype "passive"))
      (node (ref "C4") (pin "2") (pinfunction "2_2") (pintype "passive"))
      (node (ref "C5") (pin "1") (pinfunction "1_1") (pintype "passive"))
      (node (ref "D6") (pin "2") (pinfunction "CATHODE_2") (pintype "passive"))
      (node (ref "Q3") (pin "3") (pinfunction "D_3") (pintype "passive"))
      (node (ref "U1") (pin "42") (pinfunction "VBAT_42") (pintype "passive"))
      (node (ref "U1") (pin "43") (pinfunction "VBAT_43") (pintype "passive"))
    )
    (net (code "80") (name "VDD_EXT") (class "Default")
      (node (ref "C16") (pin "2") (pinfunction "2_2") (pintype "passive"))
      (node (ref "R19") (pin "1") (pinfunction "1_1") (pintype "passive"))
      (node (ref "U1") (pin "24") (pinfunction "VDD_EXT_24") (pintype "passive"))
    )
    (net (code "81") (name "unconnected-(J1-Pad2)") (class "Default")
      (node (ref "J1") (pin "2") (pinfunction "2_2") (pintype "passive"))
    )
    (net (code "82") (name "unconnected-(J1-Pad4)") (class "Default")
      (node (ref "J1") (pin "4") (pinfunction "4_4") (pintype "passive"))
    )
    (net (code "83") (name "unconnected-(J1-Pad6)") (class "Default")
      (node (ref "J1") (pin "6") (pinfunction "6_6") (pintype "passive"))
    )
    (net (code "84") (name "unconnected-(J1-Pad8)") (class "Default")
      (node (ref "J1") (pin "8") (pinfunction "8_8") (pintype "passive"))
    )
    (net (code "85") (name "unconnected-(J1-Pad10)") (class "Default")
      (node (ref "J1") (pin "10") (pinfunction "10_10") (pintype "passive"))
    )
    (net (code "86") (name "unconnected-(J1-Pad12)") (class "Default")
      (node (ref "J1") (pin "12") (pinfunction "12_12") (pintype "passive"))
    )
    (net (code "87") (name "unconnected-(J1-Pad14)") (class "Default")
      (node (ref "J1") (pin "14") (pinfunction "14_14") (pintype "passive"))
    )
    (net (code "88") (name "unconnected-(J1-Pad16)") (class "Default")
      (node (ref "J1") (pin "16") (pinfunction "16_16") (pintype "passive"))
    )
    (net (code "89") (name "unconnected-(J1-Pad18)") (class "Default")
      (node (ref "J1") (pin "18") (pinfunction "18_18") (pintype "passive"))
    )
    (net (code "90") (name "unconnected-(J2-Pad12)") (class "Default")
      (node (ref "J2") (pin "12") (pinfunction "12_12") (pintype "passive"))
    )
    (net (code "91") (name "unconnected-(J3-VPP-PadC6)") (class "Default")
      (node (ref "J3") (pin "C6") (pinfunction "VPP_C6") (pintype "passive"))
    )
    (net (code "92") (name "unconnected-(U1A-ADC-Pad9)") (class "Default")
      (node (ref "U1") (pin "9") (pinfunction "ADC_9") (pintype "passive"))
    )
    (net (code "93") (name "unconnected-(U1A-DBG_RXD-Pad38)") (class "Default")
      (node (ref "U1") (pin "38") (pinfunction "DBG_RXD_38") (pintype "passive"))
    )
    (net (code "94") (name "unconnected-(U1A-DBG_TXD-Pad39)") (class "Default")
      (node (ref "U1") (pin "39") (pinfunction "DBG_TXD_39") (pintype "passive"))
    )
    (net (code "95") (name "unconnected-(U1A-NETLIGHT-Pad16)") (class "Default")
      (node (ref "U1") (pin "16") (pinfunction "NETLIGHT_16") (pintype "passive"))
    )
    (net (code "96") (name "unconnected-(U1A-RESERVED-Pad2)") (class "Default")
      (node (ref "U1") (pin "2") (pinfunction "RESERVED_2") (pintype "passive"))
    )
    (net (code "97") (name "unconnected-(U1A-RESERVED-Pad3)") (class "Default")
      (node (ref "U1") (pin "3") (pinfunction "RESERVED_3") (pintype "passive"))
    )
    (net (code "98") (name "unconnected-(U1A-RESERVED-Pad4)") (class "Default")
      (node (ref "U1") (pin "4") (pinfunction "RESERVED_4") (pintype "passive"))
    )
    (net (code "99") (name "unconnected-(U1A-RESERVED-Pad5)") (class "Default")
      (node (ref "U1") (pin "5") (pinfunction "RESERVED_5") (pintype "passive"))
    )
    (net (code "100") (name "unconnected-(U1A-RESERVED-Pad6)") (class "Default")
      (node (ref "U1") (pin "6") (pinfunction "RESERVED_6") (pintype "passive"))
    )
    (net (code "101") (name "unconnected-(U1A-RESERVED-Pad7)") (class "Default")
      (node (ref "U1") (pin "7") (pinfunction "RESERVED_7") (pintype "passive"))
    )
    (net (code "102") (name "unconnected-(U1A-RESERVED-Pad8)") (class "Default")
      (node (ref "U1") (pin "8") (pinfunction "RESERVED_8") (pintype "passive"))
    )
    (net (code "103") (name "unconnected-(U1A-RESERVED-Pad19)") (class "Default")
      (node (ref "U1") (pin "19") (pinfunction "RESERVED_19") (pintype "passive"))
    )
    (net (code "104") (name "unconnected-(U1A-RESERVED-Pad21)") (class "Default")
      (node (ref "U1") (pin "21") (pinfunction "RESERVED_21") (pintype "passive"))
    )
    (net (code "105") (name "unconnected-(U1A-RESERVED-Pad22)") (class "Default")
      (node (ref "U1") (pin "22") (pinfunction "RESERVED_22") (pintype "passive"))
    )
    (net (code "106") (name "unconnected-(U1A-RESERVED-Pad23)") (class "Default")
      (node (ref "U1") (pin "23") (pinfunction "RESERVED_23") (pintype "passive"))
    )
    (net (code "107") (name "unconnected-(U1A-RESERVED-Pad25)") (class "Default")
      (node (ref "U1") (pin "25") (pinfunction "RESERVED_25") (pintype "passive"))
    )
    (net (code "108") (name "unconnected-(U1A-RESERVED-Pad26)") (class "Default")
      (node (ref "U1") (pin "26") (pinfunction "RESERVED_26") (pintype "passive"))
    )
    (net (code "109") (name "unconnected-(U1A-RESERVED-Pad28)") (class "Default")
      (node (ref "U1") (pin "28") (pinfunction "RESERVED_28") (pintype "passive"))
    )
    (net (code "110") (name "unconnected-(U1A-RESERVED-Pad29)") (class "Default")
      (node (ref "U1") (pin "29") (pinfunction "RESERVED_29") (pintype "passive"))
    )
    (net (code "111") (name "unconnected-(U1A-RESERVED-Pad30)") (class "Default")
      (node (ref "U1") (pin "30") (pinfunction "RESERVED_30") (pintype "passive"))
    )
    (net (code "112") (name "unconnected-(U1A-RESERVED-Pad31)") (class "Default")
      (node (ref "U1") (pin "31") (pinfunction "RESERVED_31") (pintype "passive"))
    )
    (net (code "113") (name "unconnected-(U1A-RESERVED-Pad32)") (class "Default")
      (node (ref "U1") (pin "32") (pinfunction "RESERVED_32") (pintype "passive"))
    )
    (net (code "114") (name "unconnected-(U1A-RESERVED-Pad33)") (class "Default")
      (node (ref "U1") (pin "33") (pinfunction "RESERVED_33") (pintype "passive"))
    )
    (net (code "115") (name "unconnected-(U1A-RESERVED-Pad44)") (class "Default")
      (node (ref "U1") (pin "44") (pinfunction "RESERVED_44") (pintype "passive"))
    )
    (net (code "116") (name "unconnected-(U1B-RESERVED-Pad45)") (class "Default")
      (node (ref "U1") (pin "45") (pinfunction "RESERVED_45") (pintype "passive"))
    )
    (net (code "117") (name "unconnected-(U1B-RESERVED-Pad46)") (class "Default")
      (node (ref "U1") (pin "46") (pinfunction "RESERVED_46") (pintype "passive"))
    )
    (net (code "118") (name "unconnected-(U1B-RESERVED-Pad47)") (class "Default")
      (node (ref "U1") (pin "47") (pinfunction "RESERVED_47") (pintype "passive"))
    )
    (net (code "119") (name "unconnected-(U1B-RESERVED-Pad48)") (class "Default")
      (node (ref "U1") (pin "48") (pinfunction "RESERVED_48") (pintype "passive"))
    )
    (net (code "120") (name "unconnected-(U1B-RESERVED-Pad49)") (class "Default")
      (node (ref "U1") (pin "49") (pinfunction "RESERVED_49") (pintype "passive"))
    )
    (net (code "121") (name "unconnected-(U1B-RESERVED-Pad50)") (class "Default")
      (node (ref "U1") (pin "50") (pinfunction "RESERVED_50") (pintype "passive"))
    )
    (net (code "122") (name "unconnected-(U1B-RESERVED-Pad51)") (class "Default")
      (node (ref "U1") (pin "51") (pinfunction "RESERVED_51") (pintype "passive"))
    )
    (net (code "123") (name "unconnected-(U1B-RESERVED-Pad52)") (class "Default")
      (node (ref "U1") (pin "52") (pinfunction "RESERVED_52") (pintype "passive"))
    )
    (net (code "124") (name "unconnected-(U1B-RESERVED-Pad53)") (class "Default")
      (node (ref "U1") (pin "53") (pinfunction "RESERVED_53") (pintype "passive"))
    )
    (net (code "125") (name "unconnected-(U1B-RESERVED-Pad54)") (class "Default")
      (node (ref "U1") (pin "54") (pinfunction "RESERVED_54") (pintype "passive"))
    )
    (net (code "126") (name "unconnected-(U1B-RESERVED-Pad55)") (class "Default")
      (node (ref "U1") (pin "55") (pinfunction "RESERVED_55") (pintype "passive"))
    )
    (net (code "127") (name "unconnected-(U1B-RESERVED-Pad56)") (class "Default")
      (node (ref "U1") (pin "56") (pinfunction "RESERVED_56") (pintype "passive"))
    )
    (net (code "128") (name "unconnected-(U1B-RESERVED-Pad57)") (class "Default")
      (node (ref "U1") (pin "57") (pinfunction "RESERVED_57") (pintype "passive"))
    )
    (net (code "129") (name "unconnected-(U1B-RESERVED-Pad58)") (class "Default")
      (node (ref "U1") (pin "58") (pinfunction "RESERVED_58") (pintype "passive"))
    )
    (net (code "130") (name "unconnected-(U3-PA8-Pad41)") (class "Default")
      (node (ref "U3") (pin "41") (pinfunction "PA8_41") (pintype "passive"))
    )
    (net (code "131") (name "unconnected-(U3-PA11-Pad44)") (class "Default")
      (node (ref "U3") (pin "44") (pinfunction "PA11_44") (pintype "passive"))
    )
    (net (code "132") (name "unconnected-(U3-PB12-Pad33)") (class "Default")
      (node (ref "U3") (pin "33") (pinfunction "PB12_33") (pintype "passive"))
    )
    (net (code "133") (name "unconnected-(U3-PC7-Pad38)") (class "Default")
      (node (ref "U3") (pin "38") (pinfunction "PC7_38") (pintype "passive"))
    )
    (net (code "134") (name "unconnected-(U3-PC12-Pad53)") (class "Default")
      (node (ref "U3") (pin "53") (pinfunction "PC12_53") (pintype "passive"))
    )
    (net (code "135") (name "unconnected-(U3-SPI2_MISO{slash}I2C2_SDA-Pad35)") (class "Default")
      (node (ref "U3") (pin "35") (pinfunction "SPI2_MISO/I2C2_SDA_35") (pintype "passive"))
    )
    (net (code "136") (name "unconnected-(U3-SPI2_MOSI-Pad36)") (class "Default")
      (node (ref "U3") (pin "36") (pinfunction "SPI2_MOSI_36") (pintype "passive"))
    )
    (net (code "137") (name "unconnected-(U3-UART4_RX-Pad52)") (class "Default")
      (node (ref "U3") (pin "52") (pinfunction "UART4_RX_52") (pintype "passive"))
    )
    (net (code "138") (name "unconnected-(U3-UART4_TX-Pad51)") (class "Default")
      (node (ref "U3") (pin "51") (pinfunction "UART4_TX_51") (pintype "passive"))
    )
    (net (code "139") (name "unconnected-(U3-WKUP2-Pad2)") (class "Default")
      (node (ref "U3") (pin "2") (pinfunction "WKUP2_2") (pintype "passive"))
    )
    (net (code "140") (name "unconnected-(U5-ADJ-Pad4)") (class "Default")
      (node (ref "U5") (pin "4") (pinfunction "ADJ_4") (pintype "passive"))
    )
    (net (code "141") (name "unconnected-(U6-KEY+-Pad18)") (class "Default")
      (node (ref "U6") (pin "18") (pinfunction "KEY+_18") (pintype "passive"))
    )
    (net (code "142") (name "unconnected-(U6-LED1-Pad16)") (class "Default")
      (node (ref "U6") (pin "16") (pinfunction "LED1_16") (pintype "passive"))
    )
    (net (code "143") (name "unconnected-(U6-LEDCON-Pad14)") (class "Default")
      (node (ref "U6") (pin "14") (pinfunction "LEDCON_14") (pintype "passive"))
    )
    (net (code "144") (name "unconnected-(U6-LPOUT-Pad20)") (class "Default")
      (node (ref "U6") (pin "20") (pinfunction "LPOUT_20") (pintype "passive"))
    )
    (net (code "145") (name "unconnected-(U6-P0-Pad3)") (class "Default")
      (node (ref "U6") (pin "3") (pinfunction "P0_3") (pintype "passive"))
    )
    (net (code "146") (name "unconnected-(U6-P0-Pad4)") (class "Default")
      (node (ref "U6") (pin "4") (pinfunction "P0_4") (pintype "passive"))
    )
    (net (code "147") (name "unconnected-(U6-P0-Pad5)") (class "Default")
      (node (ref "U6") (pin "5") (pinfunction "P0_5") (pintype "passive"))
    )
    (net (code "148") (name "unconnected-(U6-P0-Pad8)") (class "Default")
      (node (ref "U6") (pin "8") (pinfunction "P0_8") (pintype "passive"))
    )
    (net (code "149") (name "unconnected-(U6-P0-Pad9)") (class "Default")
      (node (ref "U6") (pin "9") (pinfunction "P0_9") (pintype "passive"))
    )
    (net (code "150") (name "unconnected-(U6-P0-Pad10)") (class "Default")
      (node (ref "U6") (pin "10") (pinfunction "P0_10") (pintype "passive"))
    )
    (net (code "151") (name "unconnected-(U6-P0-Pad15)") (class "Default")
      (node (ref "U6") (pin "15") (pinfunction "P0_15") (pintype "passive"))
    )
    (net (code "152") (name "unconnected-(U6-P0-Pad21)") (class "Default")
      (node (ref "U6") (pin "21") (pinfunction "P0_21") (pintype "passive"))
    )
    (net (code "153") (name "unconnected-(U6-P0-Pad22)") (class "Default")
      (node (ref "U6") (pin "22") (pinfunction "P0_22") (pintype "passive"))
    )
    (net (code "154") (name "unconnected-(U6-P0-Pad23)") (class "Default")
      (node (ref "U6") (pin "23") (pinfunction "P0_23") (pintype "passive"))
    )
    (net (code "155") (name "unconnected-(U6-P0-Pad24)") (class "Default")
      (node (ref "U6") (pin "24") (pinfunction "P0_24") (pintype "passive"))
    )
    (net (code "156") (name "unconnected-(U6-P0-Pad25)") (class "Default")
      (node (ref "U6") (pin "25") (pinfunction "P0_25") (pintype "passive"))
    )
    (net (code "157") (name "unconnected-(U6-P0-Pad26)") (class "Default")
      (node (ref "U6") (pin "26") (pinfunction "P0_26") (pintype "passive"))
    )
    (net (code "158") (name "unconnected-(U6-RESET-Pad11)") (class "Default")
      (node (ref "U6") (pin "11") (pinfunction "RESET_11") (pintype "passive"))
    )
    (net (code "159") (name "unconnected-(U6-SWDCLK-Pad6)") (class "Default")
      (node (ref "U6") (pin "6") (pinfunction "SWDCLK_6") (pintype "passive"))
    )
    (net (code "160") (name "unconnected-(U6-SWDIO-Pad7)") (class "Default")
      (node (ref "U6") (pin "7") (pinfunction "SWDIO_7") (pintype "passive"))
    )
    (net (code "161") (name "unconnected-(U7-1PPS-Pad4)") (class "Default")
      (node (ref "U7") (pin "4") (pinfunction "1PPS_4") (pintype "passive"))
    )
    (net (code "162") (name "unconnected-(U7-NC-Pad7)") (class "Default")
      (node (ref "U7") (pin "7") (pinfunction "NC_7") (pintype "passive"))
    )
    (net (code "163") (name "unconnected-(U7-NC-Pad13)") (class "Default")
      (node (ref "U7") (pin "13") (pinfunction "NC_13") (pintype "passive"))
    )
    (net (code "164") (name "unconnected-(U7-NC-Pad15)") (class "Default")
      (node (ref "U7") (pin "15") (pinfunction "NC_15") (pintype "passive"))
    )
    (net (code "165") (name "unconnected-(U7-NC-Pad18)") (class "Default")
      (node (ref "U7") (pin "18") (pinfunction "NC_18") (pintype "passive"))
    )
    (net (code "166") (name "unconnected-(U7-NRESET-Pad9)") (class "Default")
      (node (ref "U7") (pin "9") (pinfunction "NRESET_9") (pintype "passive"))
    )
    (net (code "167") (name "unconnected-(U7-SCL-Pad17)") (class "Default")
      (node (ref "U7") (pin "17") (pinfunction "SCL_17") (pintype "passive"))
    )
    (net (code "168") (name "unconnected-(U7-SDA-Pad16)") (class "Default")
      (node (ref "U7") (pin "16") (pinfunction "SDA_16") (pintype "passive"))
    )
  )
)
